# mosV3_0.net
KiCad netlist of a schematic drawn in Altium Designer
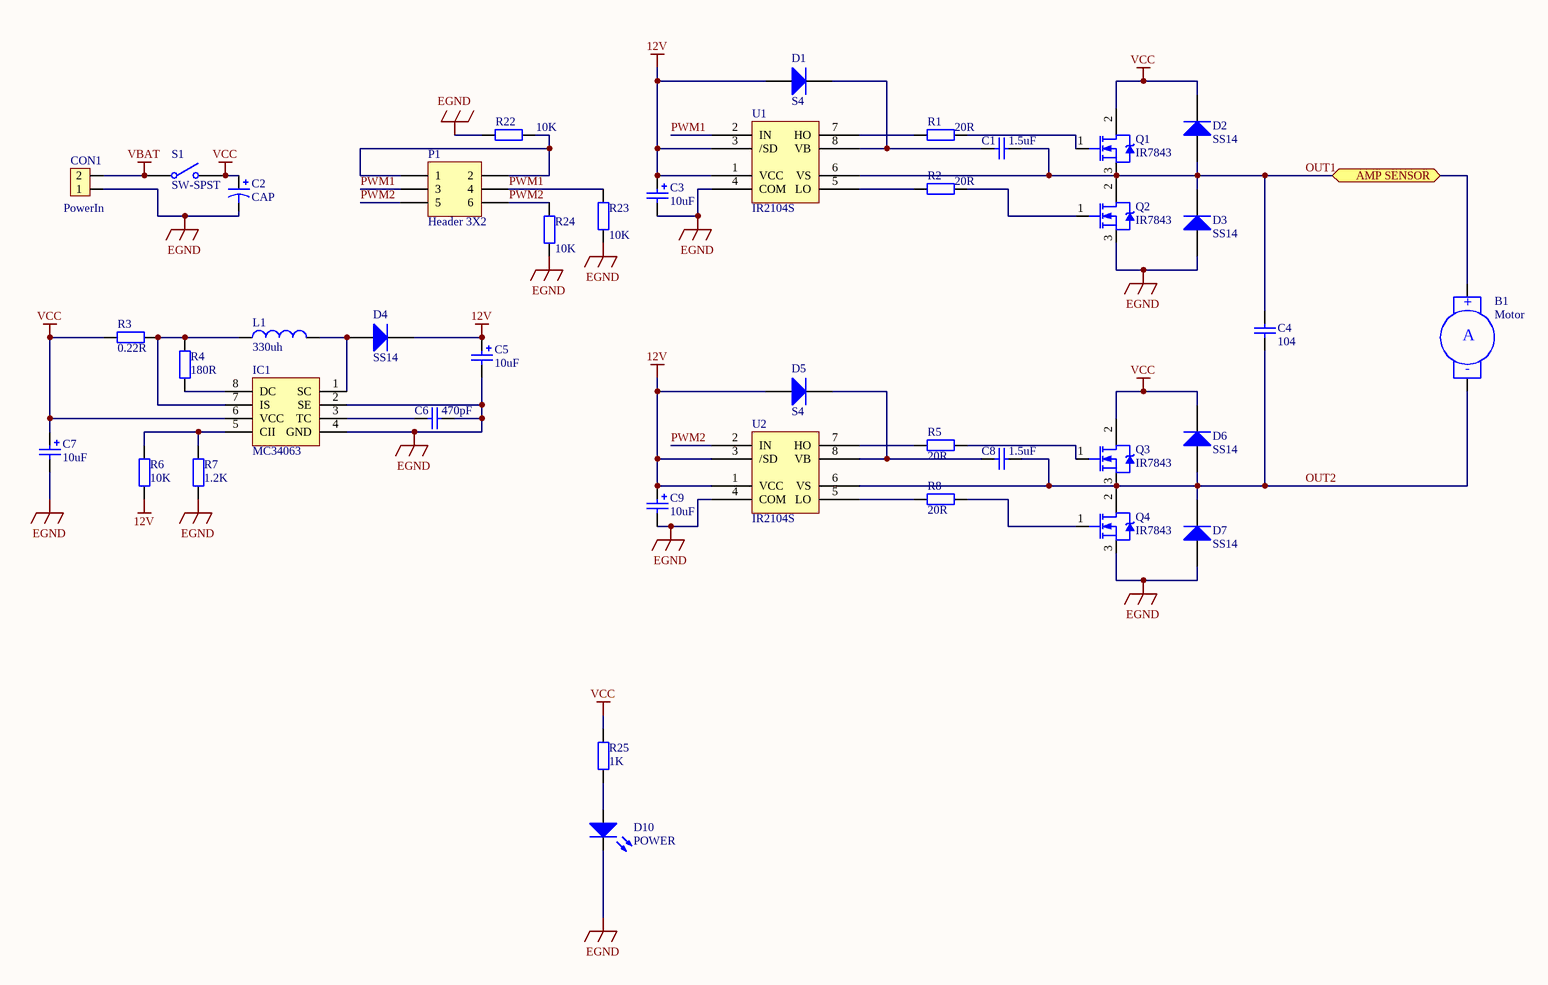
[diagram p0: 自控mosV3.0.SchDoc]

(export (version "E")
  (design (tool "Eeschema 10.0.6"))
  (components
    (comp (ref "B1")
      (value "Motor")
      (footprint "KF301-2P")
      (description "Servo Motor")
      (libsource (lib "landzo_mos") (part "Motor Servo"))
    )
    (comp (ref "C1")
      (value "1.5uF")
      (footprint "C2012")
      (description "Capacitor")
      (fields (field (name "Comment") "Cap") (field (name "PUBLISHER") "Altium Limited"))
      (libsource (lib "Miscellaneous Devices") (part "Cap"))
    )
    (comp (ref "C2") (value "CAP") (footprint "SMD-EC-F10") (libsource (lib "电赛") (part "CAP+")))
    (comp (ref "C3")
      (value "10uF")
      (footprint "C2012")
      (description "Polarized Capacitor (Radial)")
      (fields (field (name "Comment") "Cap Pol1") (field (name "PUBLISHER") "Altium Limited"))
      (libsource (lib "landzo_mos") (part "Cap Pol1"))
    )
    (comp (ref "C4")
      (value "104")
      (footprint "C2012")
      (description "Capacitor")
      (fields (field (name "Comment") "Cap") (field (name "PUBLISHER") "Altium Limited"))
      (libsource (lib "Miscellaneous Devices") (part "Cap"))
    )
    (comp (ref "C5")
      (value "10uF")
      (footprint "1206C")
      (description "Polarized Capacitor (Radial)")
      (fields (field (name "Comment") "Cap Pol1") (field (name "PUBLISHER") "Altium Limited"))
      (libsource (lib "landzo_mos") (part "Cap Pol1"))
    )
    (comp (ref "C6")
      (value "470pF")
      (footprint "C2012")
      (description "Capacitor")
      (fields (field (name "Comment") "Cap") (field (name "PUBLISHER") "Altium Limited"))
      (libsource (lib "Miscellaneous Devices") (part "Cap"))
    )
    (comp (ref "C7")
      (value "10uF")
      (footprint "1206C")
      (description "Polarized Capacitor (Radial)")
      (fields (field (name "Comment") "Cap Pol1") (field (name "PUBLISHER") "Altium Limited"))
      (libsource (lib "landzo_mos") (part "Cap Pol1"))
    )
    (comp (ref "C8")
      (value "1.5uF")
      (footprint "C2012")
      (description "Capacitor")
      (fields (field (name "Comment") "Cap") (field (name "PUBLISHER") "Altium Limited"))
      (libsource (lib "Miscellaneous Devices") (part "Cap"))
    )
    (comp (ref "C9")
      (value "10uF")
      (footprint "C2012")
      (description "Polarized Capacitor (Radial)")
      (fields (field (name "Comment") "Cap Pol1") (field (name "PUBLISHER") "Altium Limited"))
      (libsource (lib "landzo_mos") (part "Cap Pol1"))
    )
    (comp (ref "CON1")
      (value "PowerIn")
      (footprint "KF301-2P")
      (description "Header, 2-Pin")
      (libsource (lib "landzo_mos") (part "Header 2"))
    )
    (comp (ref "D1")
      (value "S4")
      (footprint "R2012")
      (description "1 Amp General Purpose Rectifier")
      (fields (field (name "PUBLISHER") "Altium Limited"))
      (libsource (lib "Miscellaneous Devices") (part "Diode 1N4007"))
    )
    (comp (ref "D2")
      (value "SS14")
      (footprint "hole-chip diode")
      (description "1 Amp General Purpose Rectifier")
      (fields (field (name "PUBLISHER") "Altium Limited"))
      (libsource (lib "Miscellaneous Devices") (part "Diode 1N4007"))
    )
    (comp (ref "D3")
      (value "SS14")
      (footprint "hole-chip diode")
      (description "1 Amp General Purpose Rectifier")
      (fields (field (name "PUBLISHER") "Altium Limited"))
      (libsource (lib "Miscellaneous Devices") (part "Diode 1N4007"))
    )
    (comp (ref "D4")
      (value "SS14")
      (footprint "hole-chip diode")
      (description "1 Amp General Purpose Rectifier")
      (fields (field (name "PUBLISHER") "Altium Limited"))
      (libsource (lib "Miscellaneous Devices") (part "Diode 1N4007"))
    )
    (comp (ref "D5")
      (value "S4")
      (footprint "R2012")
      (description "1 Amp General Purpose Rectifier")
      (fields (field (name "PUBLISHER") "Altium Limited"))
      (libsource (lib "Miscellaneous Devices") (part "Diode 1N4007"))
    )
    (comp (ref "D6")
      (value "SS14")
      (footprint "hole-chip diode")
      (description "1 Amp General Purpose Rectifier")
      (fields (field (name "PUBLISHER") "Altium Limited"))
      (libsource (lib "Miscellaneous Devices") (part "Diode 1N4007"))
    )
    (comp (ref "D7")
      (value "SS14")
      (footprint "hole-chip diode")
      (description "1 Amp General Purpose Rectifier")
      (fields (field (name "PUBLISHER") "Altium Limited"))
      (libsource (lib "Miscellaneous Devices") (part "Diode 1N4007"))
    )
    (comp (ref "D10")
      (value "POWER")
      (footprint "C2012")
      (description "Typical INFRARED GaAs LED")
      (libsource (lib "K60-V4.0") (part "LED"))
    )
    (comp (ref "IC1")
      (value "MC34063")
      (footprint "MOS motor driving module:MC34063")
      (libsource (lib "Landzo") (part "MC34063"))
    )
    (comp (ref "L1")
      (value "330uh")
      (footprint "SMD-EC-F10")
      (description "Inductor")
      (fields (field (name "PUBLISHER") "Altium Limited"))
      (libsource (lib "landzo_mos") (part "Inductor"))
    )
    (comp (ref "P1")
      (value "Header 3X2")
      (footprint "HDR2X3")
      (description "Header, 3-Pin, Dual row")
      (fields (field (name "PUBLISHER") "Altium Limited"))
      (libsource (lib "Miscellaneous Connectors") (part "Header 3X2"))
    )
    (comp (ref "Q1")
      (value "IR7843")
      (footprint "LR7843")
      (description "N-Channel Power MOSFET")
      (fields (field (name "PUBLISHER") "Altium Limited"))
      (libsource (lib "MOS motor driving module ") (part "NMOS-2"))
    )
    (comp (ref "Q2")
      (value "IR7843")
      (footprint "LR7843")
      (description "N-Channel Power MOSFET")
      (fields (field (name "PUBLISHER") "Altium Limited"))
      (libsource (lib "MOS motor driving module ") (part "NMOS-2"))
    )
    (comp (ref "Q3")
      (value "IR7843")
      (footprint "LR7843")
      (description "N-Channel Power MOSFET")
      (fields (field (name "PUBLISHER") "Altium Limited"))
      (libsource (lib "MOS motor driving module ") (part "NMOS-2"))
    )
    (comp (ref "Q4")
      (value "IR7843")
      (footprint "LR7843")
      (description "N-Channel Power MOSFET")
      (fields (field (name "PUBLISHER") "Altium Limited"))
      (libsource (lib "MOS motor driving module ") (part "NMOS-2"))
    )
    (comp (ref "R1")
      (value "20R")
      (footprint "R2012")
      (description "Resistor")
      (fields (field (name "Comment") "Res2") (field (name "PUBLISHER") "Altium Limited"))
      (libsource (lib "") (part "Res2_1"))
    )
    (comp (ref "R2")
      (value "20R")
      (footprint "R2012")
      (description "Resistor")
      (fields (field (name "Comment") "Res2") (field (name "PUBLISHER") "Altium Limited"))
      (libsource (lib "") (part "Res2_1"))
    )
    (comp (ref "R3")
      (value "0.22R")
      (footprint "SK54")
      (description "Resistor")
      (fields (field (name "Comment") "Res2") (field (name "PUBLISHER") "Altium Limited"))
      (libsource (lib "") (part "Res2_1"))
    )
    (comp (ref "R4")
      (value "180R")
      (footprint "R2012")
      (description "Resistor")
      (fields (field (name "Comment") "Res2") (field (name "PUBLISHER") "Altium Limited"))
      (libsource (lib "landzo_mos") (part "Res2"))
    )
    (comp (ref "R5")
      (value "20R")
      (footprint "R2012")
      (description "Resistor")
      (fields (field (name "Comment") "Res2") (field (name "PUBLISHER") "Altium Limited"))
      (libsource (lib "") (part "Res2_1"))
    )
    (comp (ref "R6")
      (value "10K")
      (footprint "R2012")
      (description "Resistor")
      (fields (field (name "Comment") "Res2") (field (name "PUBLISHER") "Altium Limited"))
      (libsource (lib "landzo_mos") (part "Res2"))
    )
    (comp (ref "R7")
      (value "1.2K")
      (footprint "R2012")
      (description "Resistor")
      (fields (field (name "Comment") "Res2") (field (name "PUBLISHER") "Altium Limited"))
      (libsource (lib "landzo_mos") (part "Res2"))
    )
    (comp (ref "R8")
      (value "20R")
      (footprint "R2012")
      (description "Resistor")
      (fields (field (name "Comment") "Res2") (field (name "PUBLISHER") "Altium Limited"))
      (libsource (lib "") (part "Res2_1"))
    )
    (comp (ref "R22")
      (value "10K")
      (footprint "1206(2)")
      (description "Resistor")
      (fields (field (name "Comment") "Res2") (field (name "PUBLISHER") "Altium Limited"))
      (libsource (lib "") (part "Res2_1"))
    )
    (comp (ref "R23")
      (value "10K")
      (footprint "R2012")
      (description "Resistor")
      (fields (field (name "Comment") "Res2") (field (name "PUBLISHER") "Altium Limited"))
      (libsource (lib "Miscellaneous Devices") (part "Res2"))
    )
    (comp (ref "R24")
      (value "10K")
      (footprint "R2012")
      (description "Resistor")
      (fields (field (name "Comment") "Res2") (field (name "PUBLISHER") "Altium Limited"))
      (libsource (lib "Miscellaneous Devices") (part "Res2"))
    )
    (comp (ref "R25")
      (value "1K")
      (footprint "R2012")
      (description "Resistor of led")
      (libsource (lib "K60-V4.0") (part "Res"))
    )
    (comp (ref "S1")
      (value "SW-SPST")
      (footprint "SW-125V6A(-)")
      (description "Single-Pole, Single-Throw Switch")
      (fields (field (name "PUBLISHER") "Altium Limited"))
      (libsource (lib "Miscellaneous Devices") (part "SW-SPST"))
    )
    (comp (ref "U1")
      (value "IR2104S")
      (footprint "IR2104")
      (libsource (lib "MOS motor driving module ") (part "Component_1_1"))
    )
    (comp (ref "U2")
      (value "IR2104S")
      (footprint "IR2104")
      (libsource (lib "MOS motor driving module ") (part "Component_1_1"))
    )
  )
  (nets
    (net (code "1") (name "/OUT1") (class "Default")
      (node (ref "B1") (pin "1") (pinfunction "+_1") (pintype "passive"))
      (node (ref "C1") (pin "1") (pinfunction "1_1") (pintype "passive"))
      (node (ref "C4") (pin "1") (pinfunction "1_1") (pintype "passive"))
      (node (ref "D2") (pin "1") (pinfunction "A_1") (pintype "passive"))
      (node (ref "D3") (pin "2") (pinfunction "K_2") (pintype "passive"))
      (node (ref "Q1") (pin "3") (pinfunction "S_3") (pintype "passive"))
      (node (ref "Q2") (pin "2") (pinfunction "D_2") (pintype "passive"))
      (node (ref "U1") (pin "6") (pinfunction "VS_6") (pintype "passive"))
    )
    (net (code "2") (name "/OUT2") (class "Default")
      (node (ref "B1") (pin "2") (pinfunction "-_2") (pintype "passive"))
      (node (ref "C4") (pin "2") (pinfunction "2_2") (pintype "passive"))
      (node (ref "C8") (pin "1") (pinfunction "1_1") (pintype "passive"))
      (node (ref "D6") (pin "1") (pinfunction "A_1") (pintype "passive"))
      (node (ref "D7") (pin "2") (pinfunction "K_2") (pintype "passive"))
      (node (ref "Q3") (pin "3") (pinfunction "S_3") (pintype "passive"))
      (node (ref "Q4") (pin "2") (pinfunction "D_2") (pintype "passive"))
      (node (ref "U2") (pin "6") (pinfunction "VS_6") (pintype "passive"))
    )
    (net (code "3") (name "/PWM1") (class "Default")
      (node (ref "P1") (pin "3") (pinfunction "3_3") (pintype "passive"))
      (node (ref "P1") (pin "4") (pinfunction "4_4") (pintype "passive"))
      (node (ref "R23") (pin "2") (pinfunction "2_2") (pintype "passive"))
      (node (ref "U1") (pin "2") (pinfunction "IN_2") (pintype "passive"))
    )
    (net (code "4") (name "/PWM2") (class "Default")
      (node (ref "P1") (pin "5") (pinfunction "5_5") (pintype "passive"))
      (node (ref "P1") (pin "6") (pinfunction "6_6") (pintype "passive"))
      (node (ref "R24") (pin "2") (pinfunction "2_2") (pintype "passive"))
      (node (ref "U2") (pin "2") (pinfunction "IN_2") (pintype "passive"))
    )
    (net (code "5") (name "12V") (class "Default")
      (node (ref "C3") (pin "1") (pinfunction "1_1") (pintype "passive"))
      (node (ref "C5") (pin "1") (pinfunction "1_1") (pintype "passive"))
      (node (ref "C9") (pin "1") (pinfunction "1_1") (pintype "passive"))
      (node (ref "D1") (pin "1") (pinfunction "A_1") (pintype "passive"))
      (node (ref "D4") (pin "2") (pinfunction "K_2") (pintype "passive"))
      (node (ref "D5") (pin "1") (pinfunction "A_1") (pintype "passive"))
      (node (ref "R6") (pin "1") (pinfunction "1_1") (pintype "passive"))
      (node (ref "U1") (pin "1") (pinfunction "VCC_1") (pintype "passive"))
      (node (ref "U1") (pin "3") (pinfunction "/SD_3") (pintype "passive"))
      (node (ref "U2") (pin "1") (pinfunction "VCC_1") (pintype "passive"))
      (node (ref "U2") (pin "3") (pinfunction "/SD_3") (pintype "passive"))
    )
    (net (code "6") (name "EGND") (class "Default")
      (node (ref "C2") (pin "2") (pinfunction "2_2") (pintype "passive"))
      (node (ref "C3") (pin "2") (pinfunction "2_2") (pintype "passive"))
      (node (ref "C5") (pin "2") (pinfunction "2_2") (pintype "passive"))
      (node (ref "C6") (pin "1") (pinfunction "1_1") (pintype "passive"))
      (node (ref "C7") (pin "2") (pinfunction "2_2") (pintype "passive"))
      (node (ref "C9") (pin "2") (pinfunction "2_2") (pintype "passive"))
      (node (ref "CON1") (pin "1") (pinfunction "1_1") (pintype "passive"))
      (node (ref "D10") (pin "2") (pinfunction "2_2") (pintype "passive"))
      (node (ref "D3") (pin "1") (pinfunction "A_1") (pintype "passive"))
      (node (ref "D7") (pin "1") (pinfunction "A_1") (pintype "passive"))
      (node (ref "IC1") (pin "2") (pinfunction "SE_2") (pintype "passive"))
      (node (ref "IC1") (pin "4") (pinfunction "GND_4") (pintype "passive"))
      (node (ref "Q2") (pin "3") (pinfunction "S_3") (pintype "passive"))
      (node (ref "Q4") (pin "3") (pinfunction "S_3") (pintype "passive"))
      (node (ref "R22") (pin "1") (pinfunction "1_1") (pintype "passive"))
      (node (ref "R23") (pin "1") (pinfunction "1_1") (pintype "passive"))
      (node (ref "R24") (pin "1") (pinfunction "1_1") (pintype "passive"))
      (node (ref "R7") (pin "1") (pinfunction "1_1") (pintype "passive"))
      (node (ref "U1") (pin "4") (pinfunction "COM_4") (pintype "passive"))
      (node (ref "U2") (pin "4") (pinfunction "COM_4") (pintype "passive"))
    )
    (net (code "7") (name "Net-(D1-K)") (class "Default")
      (node (ref "C1") (pin "2") (pinfunction "2_2") (pintype "passive"))
      (node (ref "D1") (pin "2") (pinfunction "K_2") (pintype "passive"))
      (node (ref "U1") (pin "8") (pinfunction "VB_8") (pintype "passive"))
    )
    (net (code "8") (name "Net-(D4-A)") (class "Default")
      (node (ref "D4") (pin "1") (pinfunction "A_1") (pintype "passive"))
      (node (ref "IC1") (pin "1") (pinfunction "SC_1") (pintype "passive"))
      (node (ref "L1") (pin "2") (pinfunction "2_2") (pintype "passive"))
    )
    (net (code "9") (name "Net-(D5-K)") (class "Default")
      (node (ref "C8") (pin "2") (pinfunction "2_2") (pintype "passive"))
      (node (ref "D5") (pin "2") (pinfunction "K_2") (pintype "passive"))
      (node (ref "U2") (pin "8") (pinfunction "VB_8") (pintype "passive"))
    )
    (net (code "10") (name "Net-(D10-Pad1)") (class "Default")
      (node (ref "D10") (pin "1") (pinfunction "1_1") (pintype "passive"))
      (node (ref "R25") (pin "1") (pinfunction "1_1") (pintype "passive"))
    )
    (net (code "11") (name "Net-(IC1-CII)") (class "Default")
      (node (ref "IC1") (pin "5") (pinfunction "CII_5") (pintype "passive"))
      (node (ref "R6") (pin "2") (pinfunction "2_2") (pintype "passive"))
      (node (ref "R7") (pin "2") (pinfunction "2_2") (pintype "passive"))
    )
    (net (code "12") (name "Net-(IC1-DC)") (class "Default")
      (node (ref "IC1") (pin "8") (pinfunction "DC_8") (pintype "passive"))
      (node (ref "R4") (pin "1") (pinfunction "1_1") (pintype "passive"))
    )
    (net (code "13") (name "Net-(IC1-IS)") (class "Default")
      (node (ref "IC1") (pin "7") (pinfunction "IS_7") (pintype "passive"))
      (node (ref "L1") (pin "1") (pinfunction "1_1") (pintype "passive"))
      (node (ref "R3") (pin "2") (pinfunction "2_2") (pintype "passive"))
      (node (ref "R4") (pin "2") (pinfunction "2_2") (pintype "passive"))
    )
    (net (code "14") (name "Net-(IC1-TC)") (class "Default")
      (node (ref "C6") (pin "2") (pinfunction "2_2") (pintype "passive"))
      (node (ref "IC1") (pin "3") (pinfunction "TC_3") (pintype "passive"))
    )
    (net (code "15") (name "Net-(P1-Pad1)") (class "Default")
      (node (ref "P1") (pin "1") (pinfunction "1_1") (pintype "passive"))
      (node (ref "P1") (pin "2") (pinfunction "2_2") (pintype "passive"))
      (node (ref "R22") (pin "2") (pinfunction "2_2") (pintype "passive"))
    )
    (net (code "16") (name "Net-(Q1-G)") (class "Default")
      (node (ref "Q1") (pin "1") (pinfunction "G_1") (pintype "passive"))
      (node (ref "R1") (pin "2") (pinfunction "2_2") (pintype "passive"))
    )
    (net (code "17") (name "Net-(Q2-G)") (class "Default")
      (node (ref "Q2") (pin "1") (pinfunction "G_1") (pintype "passive"))
      (node (ref "R2") (pin "2") (pinfunction "2_2") (pintype "passive"))
    )
    (net (code "18") (name "Net-(Q3-G)") (class "Default")
      (node (ref "Q3") (pin "1") (pinfunction "G_1") (pintype "passive"))
      (node (ref "R5") (pin "2") (pinfunction "2_2") (pintype "passive"))
    )
    (net (code "19") (name "Net-(Q4-G)") (class "Default")
      (node (ref "Q4") (pin "1") (pinfunction "G_1") (pintype "passive"))
      (node (ref "R8") (pin "2") (pinfunction "2_2") (pintype "passive"))
    )
    (net (code "20") (name "Net-(U1-HO)") (class "Default")
      (node (ref "R1") (pin "1") (pinfunction "1_1") (pintype "passive"))
      (node (ref "U1") (pin "7") (pinfunction "HO_7") (pintype "passive"))
    )
    (net (code "21") (name "Net-(U1-LO)") (class "Default")
      (node (ref "R2") (pin "1") (pinfunction "1_1") (pintype "passive"))
      (node (ref "U1") (pin "5") (pinfunction "LO_5") (pintype "passive"))
    )
    (net (code "22") (name "Net-(U2-HO)") (class "Default")
      (node (ref "R5") (pin "1") (pinfunction "1_1") (pintype "passive"))
      (node (ref "U2") (pin "7") (pinfunction "HO_7") (pintype "passive"))
    )
    (net (code "23") (name "Net-(U2-LO)") (class "Default")
      (node (ref "R8") (pin "1") (pinfunction "1_1") (pintype "passive"))
      (node (ref "U2") (pin "5") (pinfunction "LO_5") (pintype "passive"))
    )
    (net (code "24") (name "VBAT") (class "Default")
      (node (ref "CON1") (pin "2") (pinfunction "2_2") (pintype "passive"))
      (node (ref "S1") (pin "1") (pinfunction "COMMON_1") (pintype "passive"))
    )
    (net (code "25") (name "VCC") (class "Default")
      (node (ref "C2") (pin "1") (pinfunction "1_1") (pintype "passive"))
      (node (ref "C7") (pin "1") (pinfunction "1_1") (pintype "passive"))
      (node (ref "D2") (pin "2") (pinfunction "K_2") (pintype "passive"))
      (node (ref "D6") (pin "2") (pinfunction "K_2") (pintype "passive"))
      (node (ref "IC1") (pin "6") (pinfunction "VCC_6") (pintype "passive"))
      (node (ref "Q1") (pin "2") (pinfunction "D_2") (pintype "passive"))
      (node (ref "Q3") (pin "2") (pinfunction "D_2") (pintype "passive"))
      (node (ref "R25") (pin "2") (pinfunction "2_2") (pintype "passive"))
      (node (ref "R3") (pin "1") (pinfunction "1_1") (pintype "passive"))
      (node (ref "S1") (pin "2") (pinfunction "NO_2") (pintype "passive"))
    )
  )
)
